# untitled.net
KiCad netlist of a schematic drawn in EAGLE
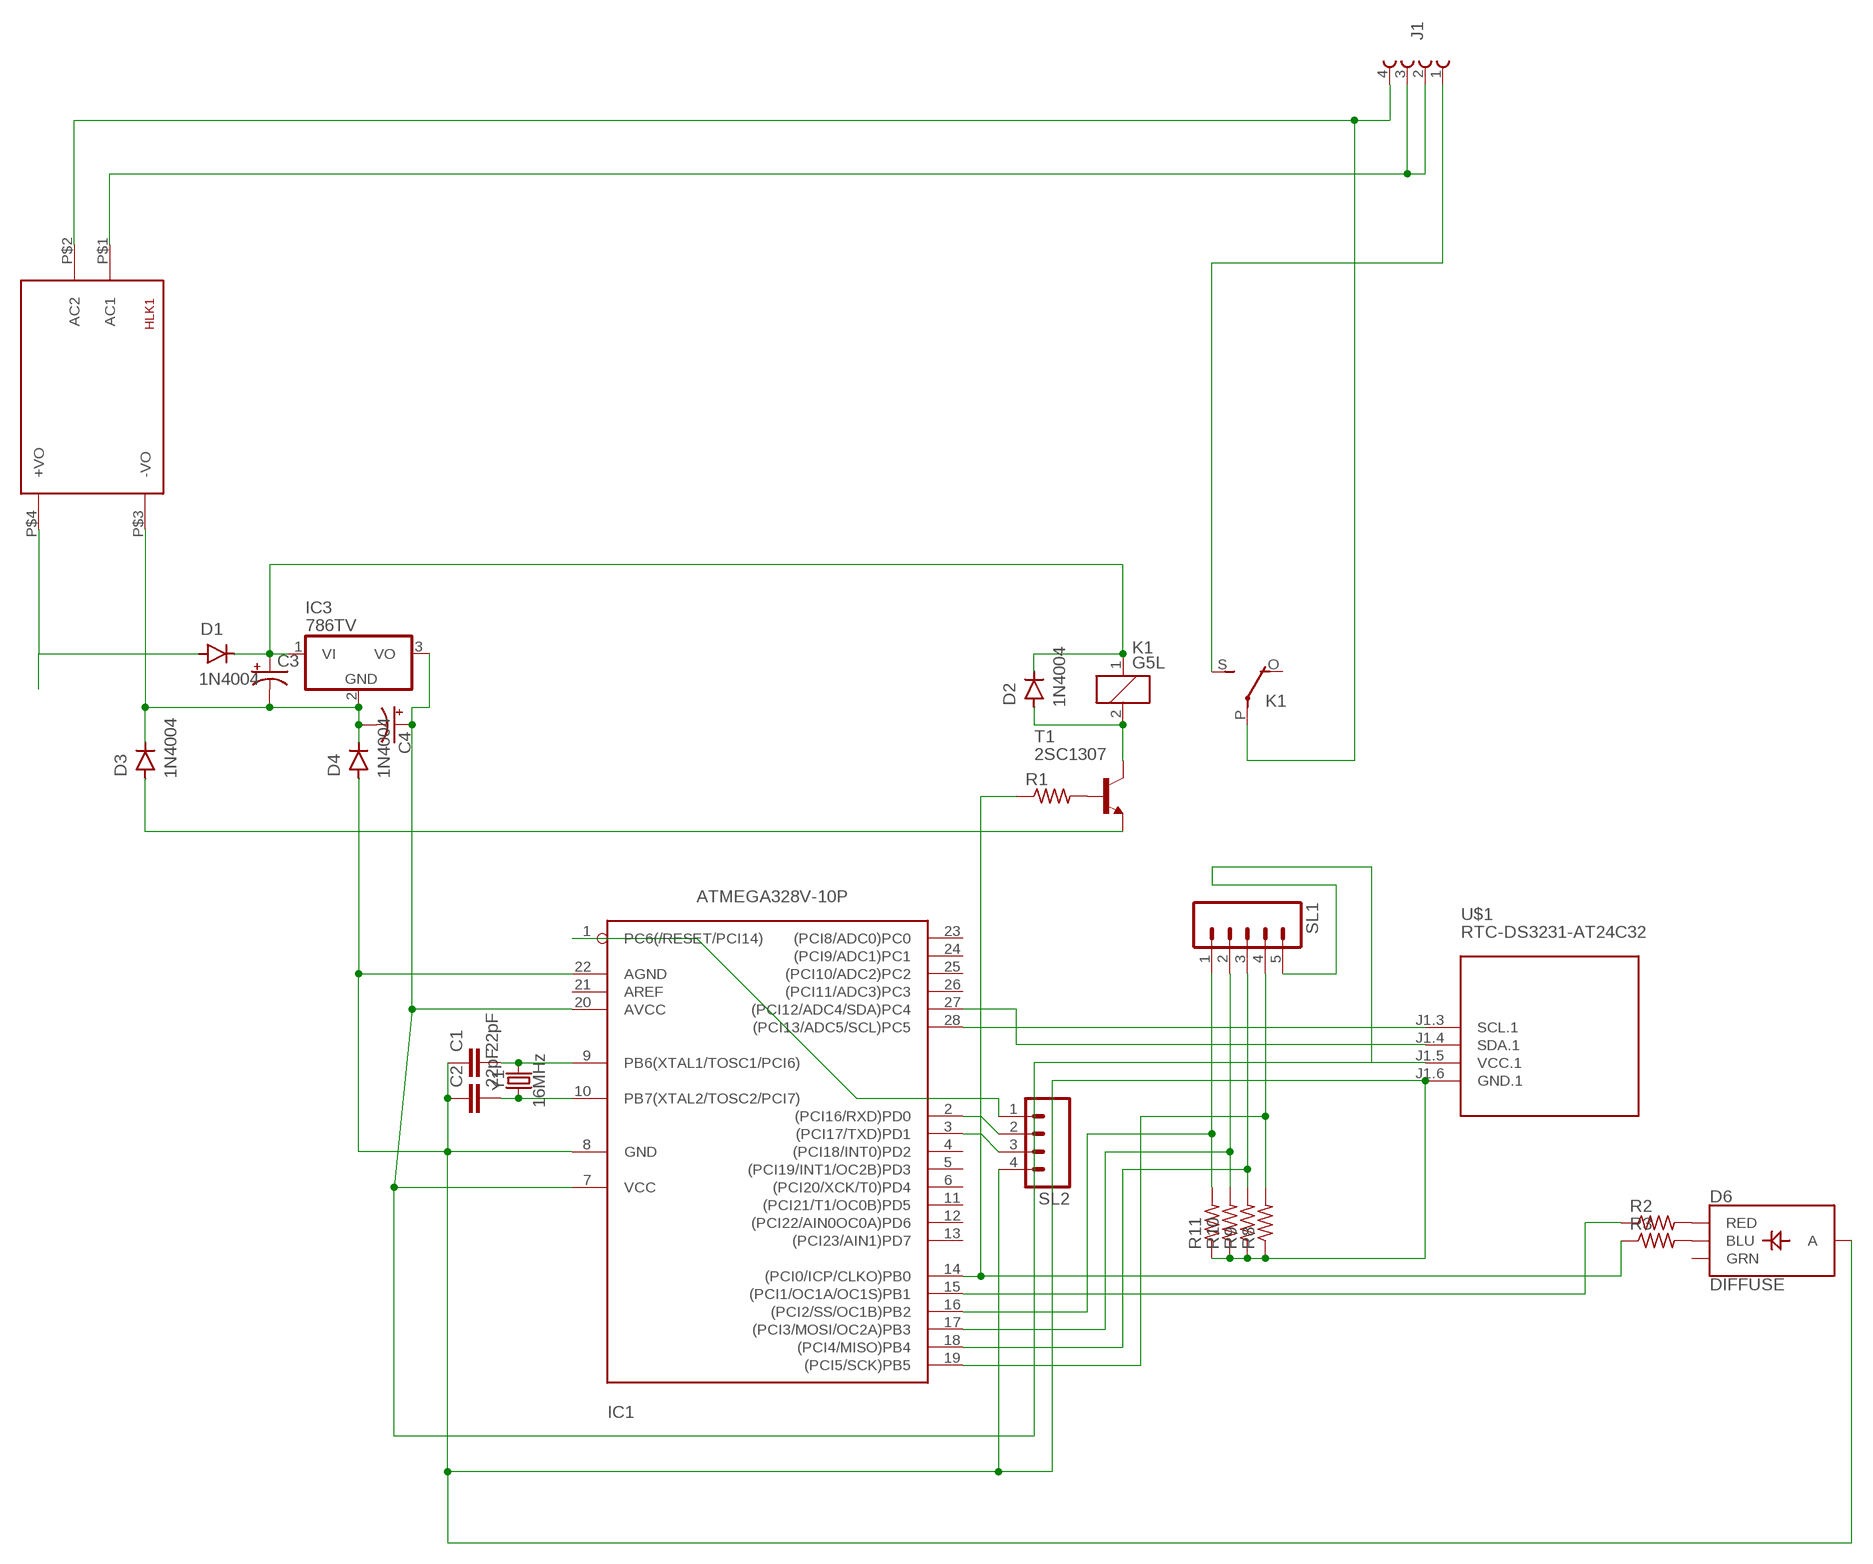
[diagram p0: schematic, sheet 1]

(export (version "E")
  (design (tool "Eeschema 10.0.6"))
  (components
    (comp (ref "C1")
      (value "22pF")
      (footprint "eagle-import:CAP-PTH-2.54")
      (libsource (lib "eagle-import") (part "22PF-PTH-2.54MM-200V-5%"))
    )
    (comp (ref "C2")
      (value "22pF")
      (footprint "eagle-import:CAP-PTH-2.54")
      (libsource (lib "eagle-import") (part "22PF-PTH-2.54MM-200V-5%"))
    )
    (comp (ref "C3")
      (value "CPOL-USE2-4")
      (footprint "eagle-import:E2-4")
      (libsource (lib "eagle-import") (part "CPOL-USE2-4"))
    )
    (comp (ref "C4")
      (value "CPOL-USE2-4")
      (footprint "eagle-import:E2-4")
      (libsource (lib "eagle-import") (part "CPOL-USE2-4"))
    )
    (comp (ref "D1")
      (value "1N4004")
      (footprint "eagle-import:DO-41")
      (fields
        (field (name "DIGIKEY_PART_NUMBER") "1N4004MSCT-ND")
        (field (name "MANUFACTURER") "Micro Commercial Co")
        (field (name "CREATED_BY") "PCBLayout.com")
      )
      (libsource (lib "eagle-import") (part "1N4004"))
    )
    (comp (ref "D2")
      (value "1N4004")
      (footprint "eagle-import:DO-41")
      (fields
        (field (name "DIGIKEY_PART_NUMBER") "1N4004MSCT-ND")
        (field (name "MANUFACTURER") "Micro Commercial Co")
        (field (name "CREATED_BY") "PCBLayout.com")
      )
      (libsource (lib "eagle-import") (part "1N4004"))
    )
    (comp (ref "D3")
      (value "1N4004")
      (footprint "eagle-import:DO-41")
      (fields
        (field (name "DIGIKEY_PART_NUMBER") "1N4004MSCT-ND")
        (field (name "MANUFACTURER") "Micro Commercial Co")
        (field (name "CREATED_BY") "PCBLayout.com")
      )
      (libsource (lib "eagle-import") (part "1N4004"))
    )
    (comp (ref "D4")
      (value "1N4004")
      (footprint "eagle-import:DO-41")
      (fields
        (field (name "DIGIKEY_PART_NUMBER") "1N4004MSCT-ND")
        (field (name "MANUFACTURER") "Micro Commercial Co")
        (field (name "CREATED_BY") "PCBLayout.com")
      )
      (libsource (lib "eagle-import") (part "1N4004"))
    )
    (comp (ref "D6")
      (value "DIFFUSE")
      (footprint "eagle-import:LED-RGB-THRU")
      (libsource (lib "eagle-import") (part "LED-RGB-CADIFFUSE"))
    )
    (comp (ref "HLK1")
      (value "HLK-PM013W")
      (footprint "eagle-import:HLK-PM01")
      (libsource (lib "eagle-import") (part "HLK-PM013W"))
    )
    (comp (ref "IC1")
      (value "ATMEGA328V-10P")
      (footprint "eagle-import:DIL28-3")
      (libsource (lib "eagle-import") (part "ATMEGA328PV-10"))
    )
    (comp (ref "IC3")
      (value "786TV")
      (footprint "eagle-import:TO220V")
      (libsource (lib "eagle-import") (part "78TV6"))
    )
    (comp (ref "J1")
      (value "691213500004")
      (footprint "eagle-import:691213500004")
      (libsource (lib "eagle-import") (part "691213500004"))
    )
    (comp (ref "K1")
      (value "G5L")
      (footprint "eagle-import:G5LE")
      (libsource (lib "eagle-import") (part "G5L"))
    )
    (comp (ref "R1")
      (value "R-US_0207/12")
      (footprint "eagle-import:0207_12")
      (libsource (lib "eagle-import") (part "adafruit_420_R-US_0207/12"))
    )
    (comp (ref "R2")
      (value "R-US_0207/12")
      (footprint "eagle-import:0207_12")
      (libsource (lib "eagle-import") (part "adafruit_420_R-US_0207/12"))
    )
    (comp (ref "R3")
      (value "R-US_0207/12")
      (footprint "eagle-import:0207_12")
      (libsource (lib "eagle-import") (part "adafruit_420_R-US_0207/12"))
    )
    (comp (ref "R8")
      (value "R-US_0207/12")
      (footprint "eagle-import:0207_12")
      (libsource (lib "eagle-import") (part "R-US_0207/12"))
    )
    (comp (ref "R9")
      (value "R-US_0207/12")
      (footprint "eagle-import:0207_12")
      (libsource (lib "eagle-import") (part "R-US_0207/12"))
    )
    (comp (ref "R10")
      (value "R-US_0207/12")
      (footprint "eagle-import:0207_12")
      (libsource (lib "eagle-import") (part "R-US_0207/12"))
    )
    (comp (ref "R11")
      (value "R-US_0207/12")
      (footprint "eagle-import:0207_12")
      (libsource (lib "eagle-import") (part "R-US_0207/12"))
    )
    (comp (ref "SL1")
      (value "M05")
      (footprint "eagle-import:05P")
      (libsource (lib "eagle-import") (part "M05"))
    )
    (comp (ref "SL2")
      (value "M04")
      (footprint "eagle-import:04P")
      (libsource (lib "eagle-import") (part "M04"))
    )
    (comp (ref "T1")
      (value "2SC1307")
      (footprint "eagle-import:TO220AV")
      (libsource (lib "eagle-import") (part "2SC1307"))
    )
    (comp (ref "U$1")
      (value "RTC-DS3231-AT24C32")
      (footprint "eagle-import:RTC-DS3231-AT24C32")
      (libsource (lib "eagle-import") (part "RTC-DS3231-AT24C32"))
    )
    (comp (ref "Y1")
      (value "16MHz")
      (footprint "eagle-import:HC49US")
      (libsource (lib "eagle-import") (part "CRYSTAL-16MHZPTH-HC49US"))
    )
  )
  (nets
    (net (code "1") (name "Net-(D6-A)") (class "Default")
      (node (ref "C1") (pin "1") (pinfunction "1_1") (pintype "passive"))
      (node (ref "C2") (pin "1") (pinfunction "1_1") (pintype "passive"))
      (node (ref "D4") (pin "A") (pinfunction "A_A") (pintype "passive"))
      (node (ref "D6") (pin "2") (pinfunction "A_2") (pintype "bidirectional"))
      (node (ref "IC1") (pin "22") (pinfunction "AGND_22") (pintype "bidirectional"))
      (node (ref "IC1") (pin "8") (pinfunction "GND_8") (pintype "bidirectional"))
      (node (ref "R10") (pin "1") (pinfunction "1_1") (pintype "passive"))
      (node (ref "R11") (pin "1") (pinfunction "1_1") (pintype "passive"))
      (node (ref "R8") (pin "1") (pinfunction "1_1") (pintype "passive"))
      (node (ref "R9") (pin "1") (pinfunction "1_1") (pintype "passive"))
      (node (ref "SL2") (pin "4") (pinfunction "4_4") (pintype "passive"))
      (node (ref "U$1") (pin "J1.6") (pinfunction "GND.1_J1.6") (pintype "power_in"))
    )
    (net (code "2") (name "Net-(D6-BLU)") (class "Default")
      (node (ref "D6") (pin "4") (pinfunction "BLU_4") (pintype "bidirectional"))
      (node (ref "R3") (pin "2") (pinfunction "2_2") (pintype "passive"))
    )
    (net (code "3") (name "Net-(D6-RED)") (class "Default")
      (node (ref "D6") (pin "1") (pinfunction "RED_1") (pintype "bidirectional"))
      (node (ref "R2") (pin "2") (pinfunction "2_2") (pintype "passive"))
    )
    (net (code "4") (name "Net-(HLK1-+VO)") (class "Default")
      (node (ref "D1") (pin "A") (pinfunction "A_A") (pintype "passive"))
      (node (ref "HLK1") (pin "P$4") (pinfunction "+VO_P$4") (pintype "bidirectional"))
    )
    (net (code "5") (name "Net-(HLK1--VO)") (class "Default")
      (node (ref "C3") (pin "-") (pinfunction "-_-") (pintype "passive"))
      (node (ref "C4") (pin "-") (pinfunction "-_-") (pintype "passive"))
      (node (ref "D3") (pin "C") (pinfunction "C_C") (pintype "passive"))
      (node (ref "D4") (pin "C") (pinfunction "C_C") (pintype "passive"))
      (node (ref "HLK1") (pin "P$3") (pinfunction "-VO_P$3") (pintype "bidirectional"))
      (node (ref "IC3") (pin "2") (pinfunction "GND_2") (pintype "passive"))
    )
    (net (code "6") (name "Net-(HLK1-AC1)") (class "Default")
      (node (ref "HLK1") (pin "P$1") (pinfunction "AC1_P$1") (pintype "bidirectional"))
      (node (ref "J1") (pin "2") (pinfunction "3_2") (pintype "passive"))
      (node (ref "J1") (pin "3") (pinfunction "2_3") (pintype "passive"))
    )
    (net (code "7") (name "Net-(HLK1-AC2)") (class "Default")
      (node (ref "HLK1") (pin "P$2") (pinfunction "AC2_P$2") (pintype "bidirectional"))
      (node (ref "J1") (pin "4") (pinfunction "1_4") (pintype "passive"))
      (node (ref "K1") (pin "P") (pinfunction "P_P") (pintype "passive"))
    )
    (net (code "8") (name "Net-(IC1-(PCI0{slash}ICP{slash}CLKO)PB0)") (class "Default")
      (node (ref "IC1") (pin "14") (pinfunction "(PCI0/ICP/CLKO)PB0_14") (pintype "bidirectional"))
      (node (ref "R1") (pin "1") (pinfunction "1_1") (pintype "passive"))
      (node (ref "R3") (pin "1") (pinfunction "1_1") (pintype "passive"))
    )
    (net (code "9") (name "Net-(IC1-(PCI1{slash}OC1A{slash}OC1S)PB1)") (class "Default")
      (node (ref "IC1") (pin "15") (pinfunction "(PCI1/OC1A/OC1S)PB1_15") (pintype "bidirectional"))
      (node (ref "R2") (pin "1") (pinfunction "1_1") (pintype "passive"))
    )
    (net (code "10") (name "Net-(IC1-(PCI2{slash}SS{slash}OC1B)PB2)") (class "Default")
      (node (ref "IC1") (pin "16") (pinfunction "(PCI2/SS/OC1B)PB2_16") (pintype "bidirectional"))
      (node (ref "R11") (pin "2") (pinfunction "2_2") (pintype "passive"))
      (node (ref "SL1") (pin "1") (pinfunction "1_1") (pintype "passive"))
    )
    (net (code "11") (name "Net-(IC1-(PCI3{slash}MOSI{slash}OC2A)PB3)") (class "Default")
      (node (ref "IC1") (pin "17") (pinfunction "(PCI3/MOSI/OC2A)PB3_17") (pintype "bidirectional"))
      (node (ref "R10") (pin "2") (pinfunction "2_2") (pintype "passive"))
      (node (ref "SL1") (pin "2") (pinfunction "2_2") (pintype "passive"))
    )
    (net (code "12") (name "Net-(IC1-(PCI4{slash}MISO)PB4)") (class "Default")
      (node (ref "IC1") (pin "18") (pinfunction "(PCI4/MISO)PB4_18") (pintype "bidirectional"))
      (node (ref "R9") (pin "2") (pinfunction "2_2") (pintype "passive"))
      (node (ref "SL1") (pin "3") (pinfunction "3_3") (pintype "passive"))
    )
    (net (code "13") (name "Net-(IC1-(PCI5{slash}SCK)PB5)") (class "Default")
      (node (ref "IC1") (pin "19") (pinfunction "(PCI5/SCK)PB5_19") (pintype "bidirectional"))
      (node (ref "R8") (pin "2") (pinfunction "2_2") (pintype "passive"))
      (node (ref "SL1") (pin "4") (pinfunction "4_4") (pintype "passive"))
    )
    (net (code "14") (name "Net-(IC1-(PCI12{slash}ADC4{slash}SDA)PC4)") (class "Default")
      (node (ref "IC1") (pin "27") (pinfunction "(PCI12/ADC4/SDA)PC4_27") (pintype "bidirectional"))
      (node (ref "U$1") (pin "J1.4") (pinfunction "SDA.1_J1.4") (pintype "bidirectional"))
    )
    (net (code "15") (name "Net-(IC1-(PCI13{slash}ADC5{slash}SCL)PC5)") (class "Default")
      (node (ref "IC1") (pin "28") (pinfunction "(PCI13/ADC5/SCL)PC5_28") (pintype "bidirectional"))
      (node (ref "U$1") (pin "J1.3") (pinfunction "SCL.1_J1.3") (pintype "bidirectional"))
    )
    (net (code "16") (name "Net-(IC1-(PCI16{slash}RXD)PD0)") (class "Default")
      (node (ref "IC1") (pin "2") (pinfunction "(PCI16/RXD)PD0_2") (pintype "bidirectional"))
      (node (ref "SL2") (pin "2") (pinfunction "2_2") (pintype "passive"))
    )
    (net (code "17") (name "Net-(IC1-(PCI17{slash}TXD)PD1)") (class "Default")
      (node (ref "IC1") (pin "3") (pinfunction "(PCI17/TXD)PD1_3") (pintype "bidirectional"))
      (node (ref "SL2") (pin "3") (pinfunction "3_3") (pintype "passive"))
    )
    (net (code "18") (name "Net-(IC1-AVCC)") (class "Default")
      (node (ref "C4") (pin "+") (pinfunction "+_+") (pintype "passive"))
      (node (ref "IC1") (pin "20") (pinfunction "AVCC_20") (pintype "bidirectional"))
      (node (ref "IC1") (pin "7") (pinfunction "VCC_7") (pintype "bidirectional"))
      (node (ref "IC3") (pin "3") (pinfunction "VO_3") (pintype "passive"))
      (node (ref "SL1") (pin "5") (pinfunction "5_5") (pintype "passive"))
      (node (ref "U$1") (pin "J1.5") (pinfunction "VCC.1_J1.5") (pintype "power_in"))
    )
    (net (code "19") (name "Net-(IC1-PB6(XTAL1{slash}TOSC1{slash}PCI6))") (class "Default")
      (node (ref "C1") (pin "2") (pinfunction "2_2") (pintype "passive"))
      (node (ref "IC1") (pin "9") (pinfunction "PB6(XTAL1/TOSC1/PCI6)_9") (pintype "bidirectional"))
      (node (ref "Y1") (pin "2") (pinfunction "2_2") (pintype "passive"))
    )
    (net (code "20") (name "Net-(IC1-PB7(XTAL2{slash}TOSC2{slash}PCI7))") (class "Default")
      (node (ref "C2") (pin "2") (pinfunction "2_2") (pintype "passive"))
      (node (ref "IC1") (pin "10") (pinfunction "PB7(XTAL2/TOSC2/PCI7)_10") (pintype "bidirectional"))
      (node (ref "Y1") (pin "1") (pinfunction "1_1") (pintype "passive"))
    )
    (net (code "21") (name "Net-(IC1-PC6({slash}RESET{slash}PCI14))") (class "Default")
      (node (ref "IC1") (pin "1") (pinfunction "PC6(/RESET/PCI14)_1") (pintype "bidirectional"))
      (node (ref "SL2") (pin "1") (pinfunction "1_1") (pintype "passive"))
    )
    (net (code "22") (name "Net-(IC3-VI)") (class "Default")
      (node (ref "C3") (pin "+") (pinfunction "+_+") (pintype "passive"))
      (node (ref "D1") (pin "C") (pinfunction "C_C") (pintype "passive"))
      (node (ref "D2") (pin "C") (pinfunction "C_C") (pintype "passive"))
      (node (ref "IC3") (pin "1") (pinfunction "VI_1") (pintype "input"))
      (node (ref "K1") (pin "1") (pinfunction "1_1") (pintype "passive"))
    )
    (net (code "23") (name "Net-(J1-4)") (class "Default")
      (node (ref "J1") (pin "1") (pinfunction "4_1") (pintype "passive"))
      (node (ref "K1") (pin "S") (pinfunction "S_S") (pintype "passive"))
    )
    (net (code "24") (name "Net-(T1-B)") (class "Default")
      (node (ref "R1") (pin "2") (pinfunction "2_2") (pintype "passive"))
      (node (ref "T1") (pin "1") (pinfunction "B_1") (pintype "passive"))
    )
    (net (code "25") (name "Net-(T1-C)") (class "Default")
      (node (ref "D2") (pin "A") (pinfunction "A_A") (pintype "passive"))
      (node (ref "K1") (pin "2") (pinfunction "2_2") (pintype "passive"))
      (node (ref "T1") (pin "2") (pinfunction "C_2") (pintype "passive"))
    )
    (net (code "26") (name "Net-(T1-E)") (class "Default")
      (node (ref "D3") (pin "A") (pinfunction "A_A") (pintype "passive"))
      (node (ref "T1") (pin "3") (pinfunction "E_3") (pintype "passive"))
    )
    (net (code "27") (name "unconnected-(D6-GRN-Pad3)") (class "Default")
      (node (ref "D6") (pin "3") (pinfunction "GRN_3") (pintype "bidirectional"))
    )
    (net (code "28") (name "unconnected-(IC1-(PCI8{slash}ADC0)PC0-Pad23)") (class "Default")
      (node (ref "IC1") (pin "23") (pinfunction "(PCI8/ADC0)PC0_23") (pintype "bidirectional"))
    )
    (net (code "29") (name "unconnected-(IC1-(PCI9{slash}ADC1)PC1-Pad24)") (class "Default")
      (node (ref "IC1") (pin "24") (pinfunction "(PCI9/ADC1)PC1_24") (pintype "bidirectional"))
    )
    (net (code "30") (name "unconnected-(IC1-(PCI10{slash}ADC2)PC2-Pad25)") (class "Default")
      (node (ref "IC1") (pin "25") (pinfunction "(PCI10/ADC2)PC2_25") (pintype "bidirectional"))
    )
    (net (code "31") (name "unconnected-(IC1-(PCI11{slash}ADC3)PC3-Pad26)") (class "Default")
      (node (ref "IC1") (pin "26") (pinfunction "(PCI11/ADC3)PC3_26") (pintype "bidirectional"))
    )
    (net (code "32") (name "unconnected-(IC1-(PCI18{slash}INT0)PD2-Pad4)") (class "Default")
      (node (ref "IC1") (pin "4") (pinfunction "(PCI18/INT0)PD2_4") (pintype "bidirectional"))
    )
    (net (code "33") (name "unconnected-(IC1-(PCI19{slash}INT1{slash}OC2B)PD3-Pad5)") (class "Default")
      (node (ref "IC1") (pin "5") (pinfunction "(PCI19/INT1/OC2B)PD3_5") (pintype "bidirectional"))
    )
    (net (code "34") (name "unconnected-(IC1-(PCI20{slash}XCK{slash}T0)PD4-Pad6)") (class "Default")
      (node (ref "IC1") (pin "6") (pinfunction "(PCI20/XCK/T0)PD4_6") (pintype "bidirectional"))
    )
    (net (code "35") (name "unconnected-(IC1-(PCI21{slash}T1{slash}OC0B)PD5-Pad11)") (class "Default")
      (node (ref "IC1") (pin "11") (pinfunction "(PCI21/T1/OC0B)PD5_11") (pintype "bidirectional"))
    )
    (net (code "36") (name "unconnected-(IC1-(PCI22{slash}AIN0OC0A)PD6-Pad12)") (class "Default")
      (node (ref "IC1") (pin "12") (pinfunction "(PCI22/AIN0OC0A)PD6_12") (pintype "bidirectional"))
    )
    (net (code "37") (name "unconnected-(IC1-(PCI23{slash}AIN1)PD7-Pad13)") (class "Default")
      (node (ref "IC1") (pin "13") (pinfunction "(PCI23/AIN1)PD7_13") (pintype "bidirectional"))
    )
    (net (code "38") (name "unconnected-(IC1-AREF-Pad21)") (class "Default")
      (node (ref "IC1") (pin "21") (pinfunction "AREF_21") (pintype "bidirectional"))
    )
    (net (code "39") (name "unconnected-(K1-PadO)") (class "Default")
      (node (ref "K1") (pin "O") (pinfunction "O_O") (pintype "passive"))
    )
  )
)
